# TimeTracker_TestboardV1.net
KiCad netlist of a schematic drawn in EAGLE
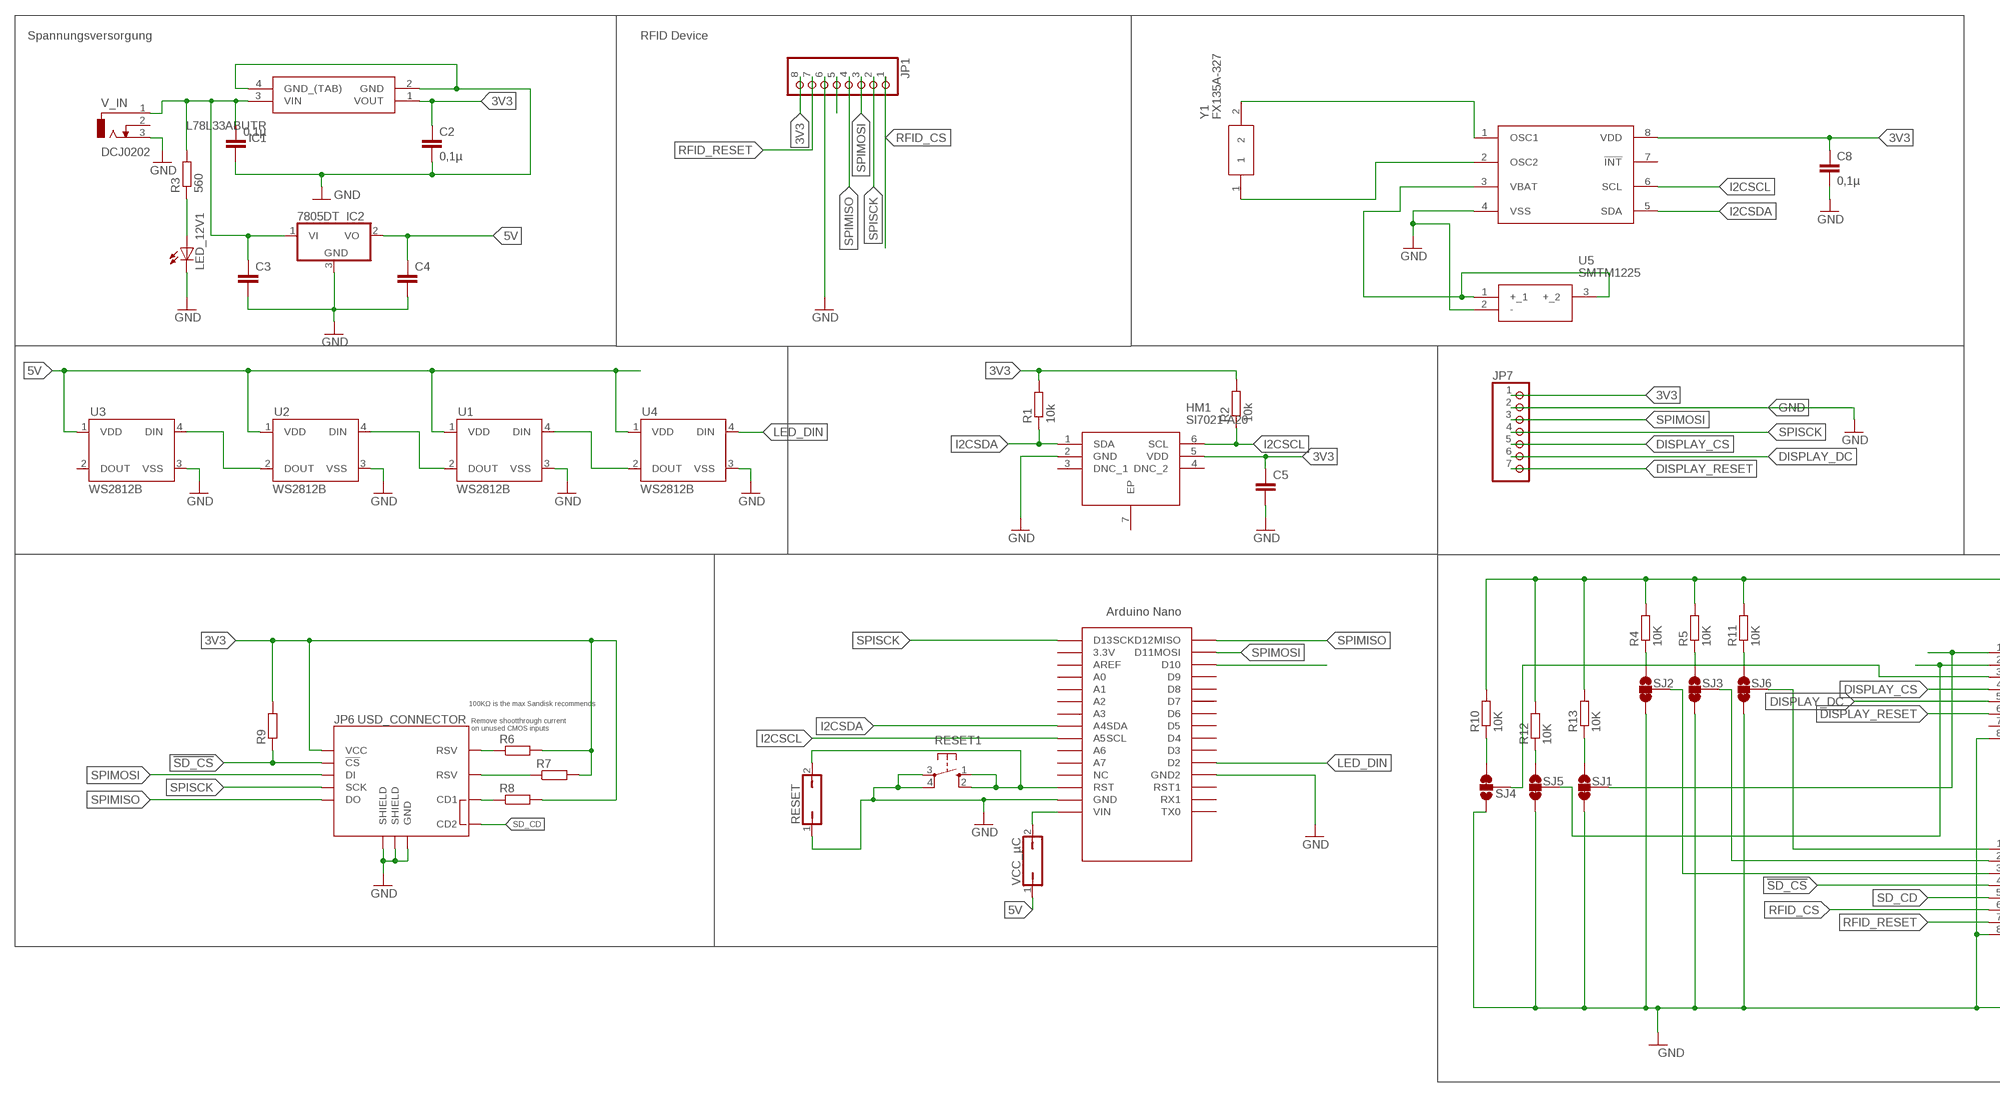
[diagram p0: schematic, sheet 1, part 1 of 2]
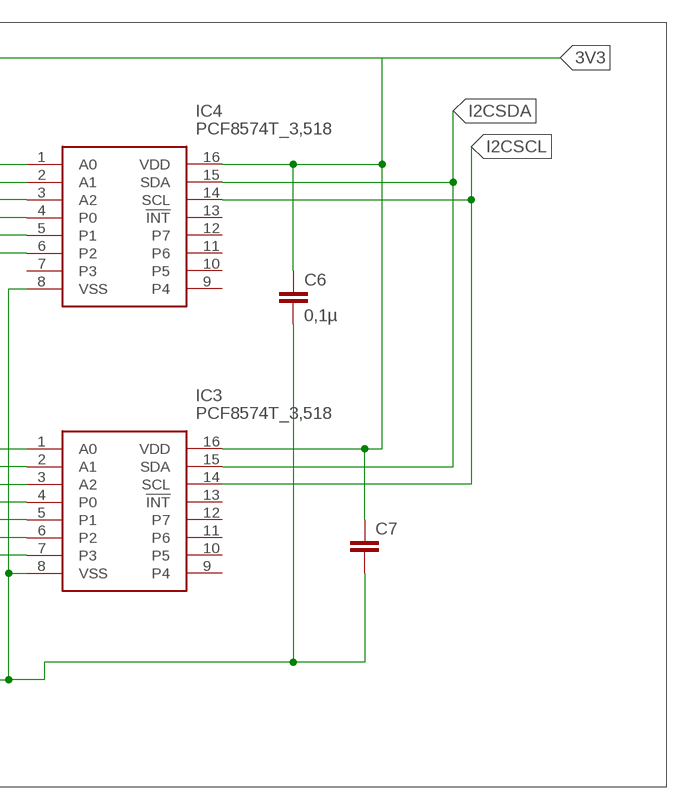
[diagram p1: schematic, sheet 1, part 2 of 2]

(export (version "E")
  (design (tool "Eeschema 10.0.6"))
  (components
    (comp (ref "0.1µ")
      (value "C-EUC0805")
      (footprint "eagle-import:C0805")
      (libsource (lib "eagle-import") (part "C-EUC0805"))
    )
    (comp (ref "C2")
      (value "0,1µ")
      (footprint "eagle-import:C0805")
      (libsource (lib "eagle-import") (part "C-EUC0805"))
    )
    (comp (ref "C3")
      (value "C-EUC0805")
      (footprint "eagle-import:C0805")
      (libsource (lib "eagle-import") (part "C-EUC0805"))
    )
    (comp (ref "C4")
      (value "C-EUC0805")
      (footprint "eagle-import:C0805")
      (libsource (lib "eagle-import") (part "C-EUC0805"))
    )
    (comp (ref "C5")
      (value "C-EUC0805")
      (footprint "eagle-import:C0805")
      (libsource (lib "eagle-import") (part "C-EUC0805"))
    )
    (comp (ref "C6")
      (value "0,1µ")
      (footprint "eagle-import:C0805")
      (libsource (lib "eagle-import") (part "C-EUC0805"))
    )
    (comp (ref "C7")
      (value "C-EUC0805")
      (footprint "eagle-import:C0805")
      (libsource (lib "eagle-import") (part "C-EUC0805"))
    )
    (comp (ref "C8")
      (value "0,1µ")
      (footprint "eagle-import:C0805")
      (libsource (lib "eagle-import") (part "C-EUC0805"))
    )
    (comp (ref "HM1")
      (value "SI7021-A20")
      (footprint "eagle-import:SON100P300X300X80-7N")
      (fields (field (name "MANUFACTURER_PART_NUMBER") "Si7021-A20"))
      (libsource (lib "eagle-import") (part "SI7021-A20"))
    )
    (comp (ref "IC1")
      (value "L78L33ABUTR")
      (footprint "eagle-import:ST-SOT-89")
      (fields
        (field (name "MOUSER_PART_NUMBER") "511-L78L33ABU-TR")
        (field (name "RS_PART_NUMBER") "6869464P")
      )
      (libsource (lib "eagle-import") (part "L78L33ABUTR"))
    )
    (comp (ref "IC2")
      (value "7805DT")
      (footprint "eagle-import:TO252")
      (libsource (lib "eagle-import") (part "78DT05"))
    )
    (comp (ref "IC3")
      (value "PCF8574T_3,518")
      (footprint "eagle-import:SOIC127P1032X265-16N")
      (fields
        (field (name "MANUFACTURER_PART_NUMBER") "PCF8574T/3,518")
        (field (name "MOUSER_PART_NUMBER") "771-PCF8574TD-T")
      )
      (libsource (lib "eagle-import") (part "PCF8574T_3,518"))
    )
    (comp (ref "IC4")
      (value "PCF8574T_3,518")
      (footprint "eagle-import:SOIC127P1032X265-16N")
      (fields
        (field (name "MANUFACTURER_PART_NUMBER") "PCF8574T/3,518")
        (field (name "MOUSER_PART_NUMBER") "771-PCF8574TD-T")
      )
      (libsource (lib "eagle-import") (part "PCF8574T_3,518"))
    )
    (comp (ref "JP1")
      (value "PINHD-1X8")
      (footprint "eagle-import:1X08")
      (libsource (lib "eagle-import") (part "PINHD-1X8"))
    )
    (comp (ref "JP6")
      (value "USD_CONNECTOR")
      (footprint "eagle-import:MICRO-SD-SOCKET-PP")
      (libsource (lib "eagle-import") (part "USD_CONNECTOR"))
    )
    (comp (ref "JP7")
      (value "PINHD-1X7")
      (footprint "eagle-import:1X07")
      (libsource (lib "eagle-import") (part "PINHD-1X7"))
    )
    (comp (ref "LED_12V1")
      (value "LEDSML0805")
      (footprint "eagle-import:SML0805")
      (libsource (lib "eagle-import") (part "LEDSML0805"))
    )
    (comp (ref "R1")
      (value "10k")
      (footprint "eagle-import:R0805")
      (libsource (lib "eagle-import") (part "R-EU_R0805"))
    )
    (comp (ref "R2")
      (value "10k")
      (footprint "eagle-import:R0805")
      (libsource (lib "eagle-import") (part "R-EU_R0805"))
    )
    (comp (ref "R3")
      (value "560")
      (footprint "eagle-import:R0805")
      (libsource (lib "eagle-import") (part "R-EU_R0805"))
    )
    (comp (ref "R4")
      (value "10K")
      (footprint "eagle-import:R0805")
      (libsource (lib "eagle-import") (part "R-EU_R0805"))
    )
    (comp (ref "R5")
      (value "10K")
      (footprint "eagle-import:R0805")
      (libsource (lib "eagle-import") (part "R-EU_R0805"))
    )
    (comp (ref "R6")
      (value "100k")
      (footprint "eagle-import:R0805")
      (libsource (lib "eagle-import") (part "R-EU_R0805"))
    )
    (comp (ref "R7")
      (value "100k")
      (footprint "eagle-import:R0805")
      (libsource (lib "eagle-import") (part "R-EU_R0805"))
    )
    (comp (ref "R8")
      (value "100k")
      (footprint "eagle-import:R0805")
      (libsource (lib "eagle-import") (part "R-EU_R0805"))
    )
    (comp (ref "R9")
      (value "100k")
      (footprint "eagle-import:R0805")
      (libsource (lib "eagle-import") (part "R-EU_R0805"))
    )
    (comp (ref "R10")
      (value "10K")
      (footprint "eagle-import:R0805")
      (libsource (lib "eagle-import") (part "R-EU_R0805"))
    )
    (comp (ref "R11")
      (value "10K")
      (footprint "eagle-import:R0805")
      (libsource (lib "eagle-import") (part "R-EU_R0805"))
    )
    (comp (ref "R12")
      (value "10K")
      (footprint "eagle-import:R0805")
      (libsource (lib "eagle-import") (part "R-EU_R0805"))
    )
    (comp (ref "R13")
      (value "10K")
      (footprint "eagle-import:R0805")
      (libsource (lib "eagle-import") (part "R-EU_R0805"))
    )
    (comp (ref "RESET")
      (value "JP1Q")
      (footprint "eagle-import:JP1")
      (libsource (lib "eagle-import") (part "JP1Q"))
    )
    (comp (ref "RESET1")
      (value "10-XX")
      (footprint "eagle-import:B3F-10XX")
      (fields (field (name "MPN") "B3F-1000"))
      (libsource (lib "eagle-import") (part "10-XX"))
    )
    (comp (ref "SJ1")
      (value "JUMPER-PAD-3-2OF3_NC_BY_TRACE_SMALL")
      (footprint "eagle-import:PAD-JUMPER-3-2OF3_NC_BY_TRACE_YES_SILK_FULL_BOX")
      (libsource (lib "eagle-import") (part "JUMPER-PAD-3-2OF3_NC_BY_TRACE_SMALL"))
    )
    (comp (ref "SJ2")
      (value "JUMPER-PAD-3-2OF3_NC_BY_TRACE_SMALL")
      (footprint "eagle-import:PAD-JUMPER-3-2OF3_NC_BY_TRACE_YES_SILK_FULL_BOX")
      (libsource (lib "eagle-import") (part "JUMPER-PAD-3-2OF3_NC_BY_TRACE_SMALL"))
    )
    (comp (ref "SJ3")
      (value "JUMPER-PAD-3-2OF3_NC_BY_TRACE_SMALL")
      (footprint "eagle-import:PAD-JUMPER-3-2OF3_NC_BY_TRACE_YES_SILK_FULL_BOX")
      (libsource (lib "eagle-import") (part "JUMPER-PAD-3-2OF3_NC_BY_TRACE_SMALL"))
    )
    (comp (ref "SJ4")
      (value "JUMPER-PAD-3-2OF3_NC_BY_TRACE_SMALL")
      (footprint "eagle-import:PAD-JUMPER-3-2OF3_NC_BY_TRACE_YES_SILK_FULL_BOX")
      (libsource (lib "eagle-import") (part "JUMPER-PAD-3-2OF3_NC_BY_TRACE_SMALL"))
    )
    (comp (ref "SJ5")
      (value "JUMPER-PAD-3-2OF3_NC_BY_TRACE_SMALL")
      (footprint "eagle-import:PAD-JUMPER-3-2OF3_NC_BY_TRACE_YES_SILK_FULL_BOX")
      (libsource (lib "eagle-import") (part "JUMPER-PAD-3-2OF3_NC_BY_TRACE_SMALL"))
    )
    (comp (ref "SJ6")
      (value "JUMPER-PAD-3-2OF3_NC_BY_TRACE_SMALL")
      (footprint "eagle-import:PAD-JUMPER-3-2OF3_NC_BY_TRACE_YES_SILK_FULL_BOX")
      (libsource (lib "eagle-import") (part "JUMPER-PAD-3-2OF3_NC_BY_TRACE_SMALL"))
    )
    (comp (ref "U$1")
      (value "NANO")
      (footprint "eagle-import:NANO")
      (libsource (lib "eagle-import") (part "NANO"))
    )
    (comp (ref "U$2")
      (value "RTC")
      (footprint "eagle-import:SOP65P490X110-8N")
      (libsource (lib "eagle-import") (part "RTC"))
    )
    (comp (ref "U1")
      (value "WS2812B")
      (footprint "eagle-import:WS2812B")
      (libsource (lib "eagle-import") (part "WS2812B"))
    )
    (comp (ref "U2")
      (value "WS2812B")
      (footprint "eagle-import:WS2812B")
      (libsource (lib "eagle-import") (part "WS2812B"))
    )
    (comp (ref "U3")
      (value "WS2812B")
      (footprint "eagle-import:WS2812B")
      (libsource (lib "eagle-import") (part "WS2812B"))
    )
    (comp (ref "U4")
      (value "WS2812B")
      (footprint "eagle-import:WS2812B")
      (libsource (lib "eagle-import") (part "WS2812B"))
    )
    (comp (ref "U5")
      (value "SMTM1225")
      (footprint "eagle-import:SMTM1225")
      (fields (field (name "MOUSER_PART_NUMBER") "614-SMTM1225"))
      (libsource (lib "eagle-import") (part "SMTM1225"))
    )
    (comp (ref "VCC_µC")
      (value "JP1Q")
      (footprint "eagle-import:JP1")
      (libsource (lib "eagle-import") (part "JP1Q"))
    )
    (comp (ref "V_IN")
      (value "DCJ0202")
      (footprint "eagle-import:DCJ0202")
      (libsource (lib "eagle-import") (part "DCJ0202"))
    )
    (comp (ref "Y1")
      (value "FX135A-327")
      (footprint "eagle-import:FX135")
      (fields (field (name "MOUSER_PART_NUMBER") "559-FX135A-327") (field (name "RS_PART_NUMBER") "6480200P"))
      (libsource (lib "eagle-import") (part "FX135A-327"))
    )
  )
  (nets
    (net (code "1") (name "/EP") (class "Default")
      (node (ref "HM1") (pin "7") (pinfunction "EP_7") (pintype "power_in"))
    )
    (net (code "2") (name "/~{SD_CS}") (class "Default")
      (node (ref "IC3") (pin "4") (pinfunction "P0_4") (pintype "bidirectional"))
      (node (ref "JP6") (pin "CS") (pinfunction "~{CS}_CS") (pintype "bidirectional"))
      (node (ref "R9") (pin "1") (pinfunction "1_1") (pintype "passive"))
    )
    (net (code "3") (name "3V3") (class "Default")
      (node (ref "C2") (pin "1") (pinfunction "1_1") (pintype "passive"))
      (node (ref "C5") (pin "1") (pinfunction "1_1") (pintype "passive"))
      (node (ref "C6") (pin "1") (pinfunction "1_1") (pintype "passive"))
      (node (ref "C7") (pin "1") (pinfunction "1_1") (pintype "passive"))
      (node (ref "C8") (pin "1") (pinfunction "1_1") (pintype "passive"))
      (node (ref "HM1") (pin "5") (pinfunction "VDD_5") (pintype "power_in"))
      (node (ref "IC1") (pin "1") (pinfunction "VOUT_1") (pintype "output"))
      (node (ref "IC3") (pin "16") (pinfunction "VDD_16") (pintype "bidirectional"))
      (node (ref "IC4") (pin "16") (pinfunction "VDD_16") (pintype "bidirectional"))
      (node (ref "JP1") (pin "8") (pinfunction "8_8") (pintype "passive"))
      (node (ref "JP6") (pin "VCC") (pinfunction "VCC_VCC") (pintype "bidirectional"))
      (node (ref "JP7") (pin "1") (pinfunction "1_1") (pintype "passive"))
      (node (ref "R1") (pin "2") (pinfunction "2_2") (pintype "passive"))
      (node (ref "R10") (pin "2") (pinfunction "2_2") (pintype "passive"))
      (node (ref "R11") (pin "2") (pinfunction "2_2") (pintype "passive"))
      (node (ref "R12") (pin "2") (pinfunction "2_2") (pintype "passive"))
      (node (ref "R13") (pin "2") (pinfunction "2_2") (pintype "passive"))
      (node (ref "R2") (pin "2") (pinfunction "2_2") (pintype "passive"))
      (node (ref "R4") (pin "2") (pinfunction "2_2") (pintype "passive"))
      (node (ref "R5") (pin "2") (pinfunction "2_2") (pintype "passive"))
      (node (ref "R6") (pin "2") (pinfunction "2_2") (pintype "passive"))
      (node (ref "R7") (pin "2") (pinfunction "2_2") (pintype "passive"))
      (node (ref "R8") (pin "2") (pinfunction "2_2") (pintype "passive"))
      (node (ref "R9") (pin "2") (pinfunction "2_2") (pintype "passive"))
      (node (ref "U$2") (pin "8") (pinfunction "VDD_8") (pintype "bidirectional"))
    )
    (net (code "4") (name "5V") (class "Default")
      (node (ref "C4") (pin "1") (pinfunction "1_1") (pintype "passive"))
      (node (ref "IC2") (pin "2") (pinfunction "VO_2") (pintype "passive"))
      (node (ref "U1") (pin "1") (pinfunction "VDD_1") (pintype "power_in"))
      (node (ref "U2") (pin "1") (pinfunction "VDD_1") (pintype "power_in"))
      (node (ref "U3") (pin "1") (pinfunction "VDD_1") (pintype "power_in"))
      (node (ref "U4") (pin "1") (pinfunction "VDD_1") (pintype "power_in"))
      (node (ref "VCC_µC") (pin "1") (pinfunction "1_1") (pintype "passive"))
    )
    (net (code "5") (name "DISPLAY_CS") (class "Default")
      (node (ref "IC4") (pin "4") (pinfunction "P0_4") (pintype "bidirectional"))
      (node (ref "JP7") (pin "5") (pinfunction "5_5") (pintype "passive"))
    )
    (net (code "6") (name "DISPLAY_DC") (class "Default")
      (node (ref "IC4") (pin "5") (pinfunction "P1_5") (pintype "bidirectional"))
      (node (ref "JP7") (pin "6") (pinfunction "6_6") (pintype "passive"))
    )
    (net (code "7") (name "DISPLAY_RESET") (class "Default")
      (node (ref "IC4") (pin "6") (pinfunction "P2_6") (pintype "bidirectional"))
      (node (ref "JP7") (pin "7") (pinfunction "7_7") (pintype "passive"))
    )
    (net (code "8") (name "GND") (class "Default")
      (node (ref "0.1µ") (pin "2") (pinfunction "2_2") (pintype "passive"))
      (node (ref "C2") (pin "2") (pinfunction "2_2") (pintype "passive"))
      (node (ref "C3") (pin "2") (pinfunction "2_2") (pintype "passive"))
      (node (ref "C4") (pin "2") (pinfunction "2_2") (pintype "passive"))
      (node (ref "C5") (pin "2") (pinfunction "2_2") (pintype "passive"))
      (node (ref "C6") (pin "2") (pinfunction "2_2") (pintype "passive"))
      (node (ref "C7") (pin "2") (pinfunction "2_2") (pintype "passive"))
      (node (ref "C8") (pin "2") (pinfunction "2_2") (pintype "passive"))
      (node (ref "HM1") (pin "2") (pinfunction "GND_2") (pintype "power_in"))
      (node (ref "IC1") (pin "2") (pinfunction "GND_2") (pintype "power_in"))
      (node (ref "IC1") (pin "4") (pinfunction "GND_(TAB)_4") (pintype "power_in"))
      (node (ref "IC2") (pin "3") (pinfunction "GND_3") (pintype "passive"))
      (node (ref "IC3") (pin "8") (pinfunction "VSS_8") (pintype "bidirectional"))
      (node (ref "IC4") (pin "8") (pinfunction "VSS_8") (pintype "bidirectional"))
      (node (ref "JP1") (pin "6") (pinfunction "6_6") (pintype "passive"))
      (node (ref "JP6") (pin "GND") (pinfunction "GND_GND") (pintype "bidirectional"))
      (node (ref "JP6") (pin "GND1") (pinfunction "SHIELD_GND1") (pintype "bidirectional"))
      (node (ref "JP6") (pin "GND3") (pinfunction "SHIELD_GND3") (pintype "bidirectional"))
      (node (ref "JP7") (pin "2") (pinfunction "2_2") (pintype "passive"))
      (node (ref "LED_12V1") (pin "C") (pinfunction "C_C") (pintype "passive"))
      (node (ref "RESET") (pin "1") (pinfunction "1_1") (pintype "passive"))
      (node (ref "RESET1") (pin "3") (pinfunction "P_3") (pintype "passive"))
      (node (ref "RESET1") (pin "4") (pinfunction "P1_4") (pintype "passive"))
      (node (ref "SJ1") (pin "3") (pinfunction "3_3") (pintype "passive"))
      (node (ref "SJ2") (pin "3") (pinfunction "3_3") (pintype "passive"))
      (node (ref "SJ3") (pin "3") (pinfunction "3_3") (pintype "passive"))
      (node (ref "SJ4") (pin "1") (pinfunction "1_1") (pintype "passive"))
      (node (ref "SJ5") (pin "3") (pinfunction "3_3") (pintype "passive"))
      (node (ref "SJ6") (pin "3") (pinfunction "3_3") (pintype "passive"))
      (node (ref "U$1") (pin "GND") (pinfunction "GND_GND") (pintype "bidirectional"))
      (node (ref "U$1") (pin "GND1") (pinfunction "GND2_GND1") (pintype "bidirectional"))
      (node (ref "U$2") (pin "4") (pinfunction "VSS_4") (pintype "bidirectional"))
      (node (ref "U1") (pin "3") (pinfunction "VSS_3") (pintype "power_in"))
      (node (ref "U2") (pin "3") (pinfunction "VSS_3") (pintype "power_in"))
      (node (ref "U3") (pin "3") (pinfunction "VSS_3") (pintype "power_in"))
      (node (ref "U4") (pin "3") (pinfunction "VSS_3") (pintype "power_in"))
      (node (ref "U5") (pin "2") (pinfunction "-_2") (pintype "bidirectional"))
      (node (ref "V_IN") (pin "3") (pinfunction "3_3") (pintype "passive"))
    )
    (net (code "9") (name "I2CSCL") (class "Default")
      (node (ref "HM1") (pin "6") (pinfunction "SCL_6") (pintype "bidirectional"))
      (node (ref "IC3") (pin "14") (pinfunction "SCL_14") (pintype "bidirectional"))
      (node (ref "IC4") (pin "14") (pinfunction "SCL_14") (pintype "bidirectional"))
      (node (ref "R2") (pin "1") (pinfunction "1_1") (pintype "passive"))
      (node (ref "U$1") (pin "A5") (pinfunction "A5SCL_A5") (pintype "bidirectional"))
      (node (ref "U$2") (pin "6") (pinfunction "SCL_6") (pintype "bidirectional"))
    )
    (net (code "10") (name "I2CSDA") (class "Default")
      (node (ref "HM1") (pin "1") (pinfunction "SDA_1") (pintype "bidirectional"))
      (node (ref "IC3") (pin "15") (pinfunction "SDA_15") (pintype "bidirectional"))
      (node (ref "IC4") (pin "15") (pinfunction "SDA_15") (pintype "bidirectional"))
      (node (ref "R1") (pin "1") (pinfunction "1_1") (pintype "passive"))
      (node (ref "U$1") (pin "A4") (pinfunction "A4SDA_A4") (pintype "bidirectional"))
      (node (ref "U$2") (pin "5") (pinfunction "SDA_5") (pintype "bidirectional"))
    )
    (net (code "11") (name "LED_DIN") (class "Default")
      (node (ref "U$1") (pin "D2") (pinfunction "D2_D2") (pintype "bidirectional"))
      (node (ref "U4") (pin "4") (pinfunction "DIN_4") (pintype "input"))
    )
    (net (code "12") (name "Net-(IC1-VIN)") (class "Default")
      (node (ref "0.1µ") (pin "1") (pinfunction "1_1") (pintype "passive"))
      (node (ref "C3") (pin "1") (pinfunction "1_1") (pintype "passive"))
      (node (ref "IC1") (pin "3") (pinfunction "VIN_3") (pintype "input"))
      (node (ref "IC2") (pin "1") (pinfunction "VI_1") (pintype "input"))
      (node (ref "R3") (pin "2") (pinfunction "2_2") (pintype "passive"))
      (node (ref "V_IN") (pin "1") (pinfunction "1_1") (pintype "passive"))
    )
    (net (code "13") (name "Net-(IC3-A0)") (class "Default")
      (node (ref "IC3") (pin "1") (pinfunction "A0_1") (pintype "bidirectional"))
      (node (ref "SJ6") (pin "2") (pinfunction "2_2") (pintype "passive"))
    )
    (net (code "14") (name "Net-(IC3-A1)") (class "Default")
      (node (ref "IC3") (pin "2") (pinfunction "A1_2") (pintype "bidirectional"))
      (node (ref "SJ3") (pin "2") (pinfunction "2_2") (pintype "passive"))
    )
    (net (code "15") (name "Net-(IC3-A2)") (class "Default")
      (node (ref "IC3") (pin "3") (pinfunction "A2_3") (pintype "bidirectional"))
      (node (ref "SJ2") (pin "2") (pinfunction "2_2") (pintype "passive"))
    )
    (net (code "16") (name "Net-(IC4-A0)") (class "Default")
      (node (ref "IC4") (pin "1") (pinfunction "A0_1") (pintype "bidirectional"))
      (node (ref "SJ1") (pin "2") (pinfunction "2_2") (pintype "passive"))
    )
    (net (code "17") (name "Net-(IC4-A1)") (class "Default")
      (node (ref "IC4") (pin "2") (pinfunction "A1_2") (pintype "bidirectional"))
      (node (ref "SJ5") (pin "2") (pinfunction "2_2") (pintype "passive"))
    )
    (net (code "18") (name "Net-(IC4-A2)") (class "Default")
      (node (ref "IC4") (pin "3") (pinfunction "A2_3") (pintype "bidirectional"))
      (node (ref "SJ4") (pin "2") (pinfunction "2_2") (pintype "passive"))
    )
    (net (code "19") (name "Net-(JP6-PadCD1)") (class "Default")
      (node (ref "JP6") (pin "CD1") (pinfunction "CD1_CD1") (pintype "bidirectional"))
      (node (ref "R8") (pin "1") (pinfunction "1_1") (pintype "passive"))
    )
    (net (code "20") (name "Net-(JP6-RSV-PadRSV1)") (class "Default")
      (node (ref "JP6") (pin "RSV1") (pinfunction "RSV_RSV1") (pintype "bidirectional"))
      (node (ref "R6") (pin "1") (pinfunction "1_1") (pintype "passive"))
    )
    (net (code "21") (name "Net-(JP6-RSV-PadRSV2)") (class "Default")
      (node (ref "JP6") (pin "RSV2") (pinfunction "RSV_RSV2") (pintype "bidirectional"))
      (node (ref "R7") (pin "1") (pinfunction "1_1") (pintype "passive"))
    )
    (net (code "22") (name "Net-(LED_12V1-PadA)") (class "Default")
      (node (ref "LED_12V1") (pin "A") (pinfunction "A_A") (pintype "passive"))
      (node (ref "R3") (pin "1") (pinfunction "1_1") (pintype "passive"))
    )
    (net (code "23") (name "Net-(R4-Pad1)") (class "Default")
      (node (ref "R4") (pin "1") (pinfunction "1_1") (pintype "passive"))
      (node (ref "SJ2") (pin "1") (pinfunction "1_1") (pintype "passive"))
    )
    (net (code "24") (name "Net-(R5-Pad1)") (class "Default")
      (node (ref "R5") (pin "1") (pinfunction "1_1") (pintype "passive"))
      (node (ref "SJ3") (pin "1") (pinfunction "1_1") (pintype "passive"))
    )
    (net (code "25") (name "Net-(R10-Pad1)") (class "Default")
      (node (ref "R10") (pin "1") (pinfunction "1_1") (pintype "passive"))
      (node (ref "SJ4") (pin "3") (pinfunction "3_3") (pintype "passive"))
    )
    (net (code "26") (name "Net-(R11-Pad1)") (class "Default")
      (node (ref "R11") (pin "1") (pinfunction "1_1") (pintype "passive"))
      (node (ref "SJ6") (pin "1") (pinfunction "1_1") (pintype "passive"))
    )
    (net (code "27") (name "Net-(R12-Pad1)") (class "Default")
      (node (ref "R12") (pin "1") (pinfunction "1_1") (pintype "passive"))
      (node (ref "SJ5") (pin "1") (pinfunction "1_1") (pintype "passive"))
    )
    (net (code "28") (name "Net-(R13-Pad1)") (class "Default")
      (node (ref "R13") (pin "1") (pinfunction "1_1") (pintype "passive"))
      (node (ref "SJ1") (pin "1") (pinfunction "1_1") (pintype "passive"))
    )
    (net (code "29") (name "Net-(RESET1-S)") (class "Default")
      (node (ref "RESET") (pin "2") (pinfunction "2_2") (pintype "passive"))
      (node (ref "RESET1") (pin "1") (pinfunction "S_1") (pintype "passive"))
      (node (ref "RESET1") (pin "2") (pinfunction "S1_2") (pintype "passive"))
      (node (ref "U$1") (pin "RST") (pinfunction "RST_RST") (pintype "bidirectional"))
    )
    (net (code "30") (name "Net-(U$1-VIN)") (class "Default")
      (node (ref "U$1") (pin "RAW") (pinfunction "VIN_RAW") (pintype "bidirectional"))
      (node (ref "VCC_µC") (pin "2") (pinfunction "2_2") (pintype "passive"))
    )
    (net (code "31") (name "Net-(U$2-OSC1)") (class "Default")
      (node (ref "U$2") (pin "1") (pinfunction "OSC1_1") (pintype "bidirectional"))
      (node (ref "Y1") (pin "2") (pinfunction "2_2") (pintype "bidirectional"))
    )
    (net (code "32") (name "Net-(U$2-OSC2)") (class "Default")
      (node (ref "U$2") (pin "2") (pinfunction "OSC2_2") (pintype "bidirectional"))
      (node (ref "Y1") (pin "1") (pinfunction "1_1") (pintype "bidirectional"))
    )
    (net (code "33") (name "Net-(U$2-VBAT)") (class "Default")
      (node (ref "U$2") (pin "3") (pinfunction "VBAT_3") (pintype "bidirectional"))
      (node (ref "U5") (pin "1") (pinfunction "+_1_1") (pintype "bidirectional"))
      (node (ref "U5") (pin "3") (pinfunction "+_2_3") (pintype "bidirectional"))
    )
    (net (code "34") (name "Net-(U1-DIN)") (class "Default")
      (node (ref "U1") (pin "4") (pinfunction "DIN_4") (pintype "input"))
      (node (ref "U4") (pin "2") (pinfunction "DOUT_2") (pintype "output"))
    )
    (net (code "35") (name "Net-(U1-DOUT)") (class "Default")
      (node (ref "U1") (pin "2") (pinfunction "DOUT_2") (pintype "output"))
      (node (ref "U2") (pin "4") (pinfunction "DIN_4") (pintype "input"))
    )
    (net (code "36") (name "Net-(U2-DOUT)") (class "Default")
      (node (ref "U2") (pin "2") (pinfunction "DOUT_2") (pintype "output"))
      (node (ref "U3") (pin "4") (pinfunction "DIN_4") (pintype "input"))
    )
    (net (code "37") (name "RFID_CS") (class "Default")
      (node (ref "IC3") (pin "6") (pinfunction "P2_6") (pintype "bidirectional"))
      (node (ref "JP1") (pin "1") (pinfunction "1_1") (pintype "passive"))
    )
    (net (code "38") (name "RFID_RESET") (class "Default")
      (node (ref "IC3") (pin "7") (pinfunction "P3_7") (pintype "bidirectional"))
      (node (ref "JP1") (pin "7") (pinfunction "7_7") (pintype "passive"))
    )
    (net (code "39") (name "SD_CD") (class "Default")
      (node (ref "IC3") (pin "5") (pinfunction "P1_5") (pintype "bidirectional"))
      (node (ref "JP6") (pin "CD2") (pinfunction "CD2_CD2") (pintype "bidirectional"))
    )
    (net (code "40") (name "SPIMISO") (class "Default")
      (node (ref "JP1") (pin "4") (pinfunction "4_4") (pintype "passive"))
      (node (ref "JP6") (pin "DO") (pinfunction "DO_DO") (pintype "bidirectional"))
      (node (ref "U$1") (pin "D12") (pinfunction "D12MISO_D12") (pintype "bidirectional"))
    )
    (net (code "41") (name "SPIMOSI") (class "Default")
      (node (ref "JP1") (pin "3") (pinfunction "3_3") (pintype "passive"))
      (node (ref "JP6") (pin "DI") (pinfunction "DI_DI") (pintype "bidirectional"))
      (node (ref "JP7") (pin "3") (pinfunction "3_3") (pintype "passive"))
      (node (ref "U$1") (pin "D11") (pinfunction "D11MOSI_D11") (pintype "bidirectional"))
    )
    (net (code "42") (name "SPISCK") (class "Default")
      (node (ref "JP1") (pin "2") (pinfunction "2_2") (pintype "passive"))
      (node (ref "JP6") (pin "SCLK") (pinfunction "SCK_SCLK") (pintype "bidirectional"))
      (node (ref "JP7") (pin "4") (pinfunction "4_4") (pintype "passive"))
      (node (ref "U$1") (pin "D13") (pinfunction "D13SCK_D13") (pintype "bidirectional"))
    )
    (net (code "43") (name "unconnected-(HM1-DNC_1-Pad3)") (class "Default")
      (node (ref "HM1") (pin "3") (pinfunction "DNC_1_3") (pintype "bidirectional"))
    )
    (net (code "44") (name "unconnected-(HM1-DNC_2-Pad4)") (class "Default")
      (node (ref "HM1") (pin "4") (pinfunction "DNC_2_4") (pintype "bidirectional"))
    )
    (net (code "45") (name "unconnected-(IC3-P4-Pad9)") (class "Default")
      (node (ref "IC3") (pin "9") (pinfunction "P4_9") (pintype "bidirectional"))
    )
    (net (code "46") (name "unconnected-(IC3-P5-Pad10)") (class "Default")
      (node (ref "IC3") (pin "10") (pinfunction "P5_10") (pintype "bidirectional"))
    )
    (net (code "47") (name "unconnected-(IC3-P6-Pad11)") (class "Default")
      (node (ref "IC3") (pin "11") (pinfunction "P6_11") (pintype "bidirectional"))
    )
    (net (code "48") (name "unconnected-(IC3-P7-Pad12)") (class "Default")
      (node (ref "IC3") (pin "12") (pinfunction "P7_12") (pintype "bidirectional"))
    )
    (net (code "49") (name "unconnected-(IC3-~{INT}-Pad13)") (class "Default")
      (node (ref "IC3") (pin "13") (pinfunction "~{INT}_13") (pintype "bidirectional"))
    )
    (net (code "50") (name "unconnected-(IC4-P3-Pad7)") (class "Default")
      (node (ref "IC4") (pin "7") (pinfunction "P3_7") (pintype "bidirectional"))
    )
    (net (code "51") (name "unconnected-(IC4-P4-Pad9)") (class "Default")
      (node (ref "IC4") (pin "9") (pinfunction "P4_9") (pintype "bidirectional"))
    )
    (net (code "52") (name "unconnected-(IC4-P5-Pad10)") (class "Default")
      (node (ref "IC4") (pin "10") (pinfunction "P5_10") (pintype "bidirectional"))
    )
    (net (code "53") (name "unconnected-(IC4-P6-Pad11)") (class "Default")
      (node (ref "IC4") (pin "11") (pinfunction "P6_11") (pintype "bidirectional"))
    )
    (net (code "54") (name "unconnected-(IC4-P7-Pad12)") (class "Default")
      (node (ref "IC4") (pin "12") (pinfunction "P7_12") (pintype "bidirectional"))
    )
    (net (code "55") (name "unconnected-(IC4-~{INT}-Pad13)") (class "Default")
      (node (ref "IC4") (pin "13") (pinfunction "~{INT}_13") (pintype "bidirectional"))
    )
    (net (code "56") (name "unconnected-(JP1-Pad5)") (class "Default")
      (node (ref "JP1") (pin "5") (pinfunction "5_5") (pintype "passive"))
    )
    (net (code "57") (name "unconnected-(U$1-NC-Pad5V)") (class "Default")
      (node (ref "U$1") (pin "5V") (pinfunction "NC_5V") (pintype "bidirectional"))
    )
    (net (code "58") (name "unconnected-(U$1-Pad3.3V)") (class "Default")
      (node (ref "U$1") (pin "3.3V") (pinfunction "3.3V_3.3V") (pintype "bidirectional"))
    )
    (net (code "59") (name "unconnected-(U$1-PadA0)") (class "Default")
      (node (ref "U$1") (pin "A0") (pinfunction "A0_A0") (pintype "bidirectional"))
    )
    (net (code "60") (name "unconnected-(U$1-PadA1)") (class "Default")
      (node (ref "U$1") (pin "A1") (pinfunction "A1_A1") (pintype "bidirectional"))
    )
    (net (code "61") (name "unconnected-(U$1-PadA2)") (class "Default")
      (node (ref "U$1") (pin "A2") (pinfunction "A2_A2") (pintype "bidirectional"))
    )
    (net (code "62") (name "unconnected-(U$1-PadA3)") (class "Default")
      (node (ref "U$1") (pin "A3") (pinfunction "A3_A3") (pintype "bidirectional"))
    )
    (net (code "63") (name "unconnected-(U$1-PadA6)") (class "Default")
      (node (ref "U$1") (pin "A6") (pinfunction "A6_A6") (pintype "bidirectional"))
    )
    (net (code "64") (name "unconnected-(U$1-PadA7)") (class "Default")
      (node (ref "U$1") (pin "A7") (pinfunction "A7_A7") (pintype "bidirectional"))
    )
    (net (code "65") (name "unconnected-(U$1-PadAREF)") (class "Default")
      (node (ref "U$1") (pin "AREF") (pinfunction "AREF_AREF") (pintype "bidirectional"))
    )
    (net (code "66") (name "unconnected-(U$1-PadD3)") (class "Default")
      (node (ref "U$1") (pin "D3") (pinfunction "D3_D3") (pintype "bidirectional"))
    )
    (net (code "67") (name "unconnected-(U$1-PadD4)") (class "Default")
      (node (ref "U$1") (pin "D4") (pinfunction "D4_D4") (pintype "bidirectional"))
    )
    (net (code "68") (name "unconnected-(U$1-PadD5)") (class "Default")
      (node (ref "U$1") (pin "D5") (pinfunction "D5_D5") (pintype "bidirectional"))
    )
    (net (code "69") (name "unconnected-(U$1-PadD6)") (class "Default")
      (node (ref "U$1") (pin "D6") (pinfunction "D6_D6") (pintype "bidirectional"))
    )
    (net (code "70") (name "unconnected-(U$1-PadD7)") (class "Default")
      (node (ref "U$1") (pin "D7") (pinfunction "D7_D7") (pintype "bidirectional"))
    )
    (net (code "71") (name "unconnected-(U$1-PadD8)") (class "Default")
      (node (ref "U$1") (pin "D8") (pinfunction "D8_D8") (pintype "bidirectional"))
    )
    (net (code "72") (name "unconnected-(U$1-PadD9)") (class "Default")
      (node (ref "U$1") (pin "D9") (pinfunction "D9_D9") (pintype "bidirectional"))
    )
    (net (code "73") (name "unconnected-(U$1-PadD10)") (class "Default")
      (node (ref "U$1") (pin "D10") (pinfunction "D10_D10") (pintype "bidirectional"))
    )
    (net (code "74") (name "unconnected-(U$1-PadRST1)") (class "Default")
      (node (ref "U$1") (pin "RST1") (pinfunction "RST1_RST1") (pintype "bidirectional"))
    )
    (net (code "75") (name "unconnected-(U$1-PadRX1)") (class "Default")
      (node (ref "U$1") (pin "RX1") (pinfunction "RX1_RX1") (pintype "bidirectional"))
    )
    (net (code "76") (name "unconnected-(U$1-PadTX0)") (class "Default")
      (node (ref "U$1") (pin "TX0") (pinfunction "TX0_TX0") (pintype "bidirectional"))
    )
    (net (code "77") (name "unconnected-(U$2-~{INT}-Pad7)") (class "Default")
      (node (ref "U$2") (pin "7") (pinfunction "~{INT}_7") (pintype "bidirectional"))
    )
    (net (code "78") (name "unconnected-(U3-DOUT-Pad2)") (class "Default")
      (node (ref "U3") (pin "2") (pinfunction "DOUT_2") (pintype "output"))
    )
    (net (code "79") (name "unconnected-(V_IN-Pad2)") (class "Default")
      (node (ref "V_IN") (pin "2") (pinfunction "2_2") (pintype "passive"))
    )
  )
)
